# CPU.net
KiCad netlist of a schematic drawn in Altium Designer
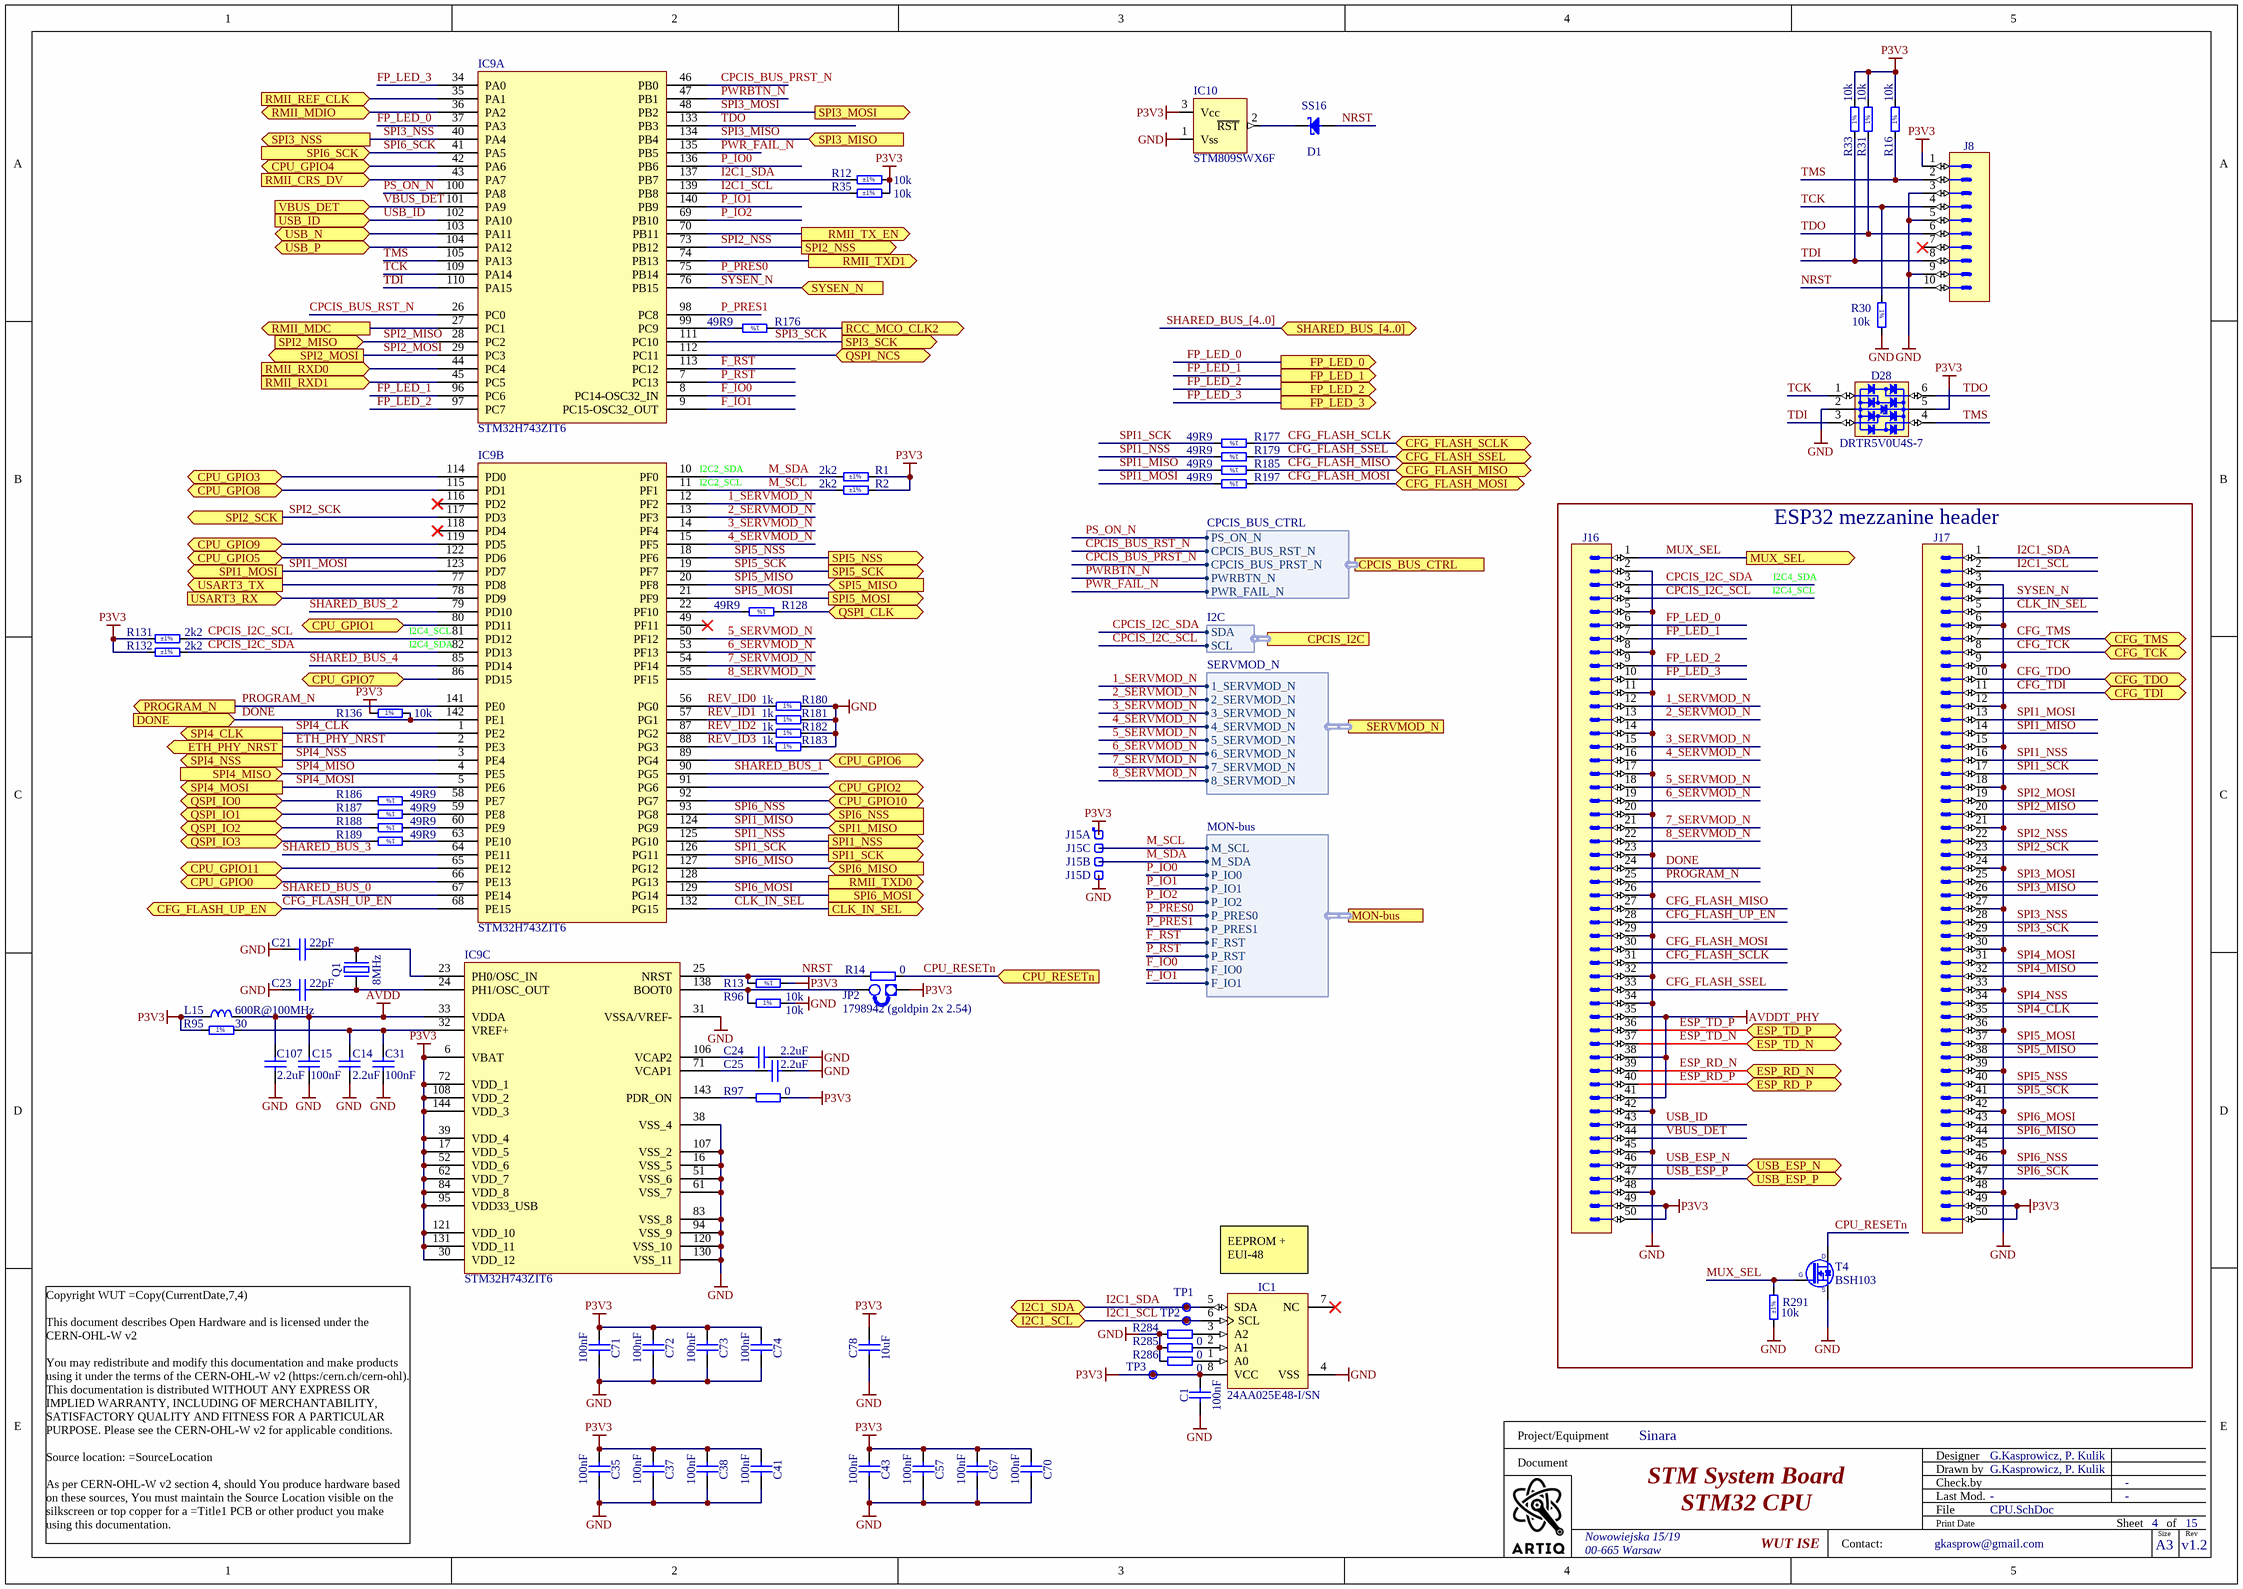
[diagram p0: CPU.SchDoc]

(export (version "E")
  (design (tool "Eeschema 10.0.6"))
  (components
    (comp (ref "C1")
      (value "100nF")
      (footprint "CAPC1005X55N")
      (description "Non-polarised capacitor")
      (fields
        (field (name "PART NUMBER") "CC0402_100NF_16V_10%_X5R")
        (field (name "VOLTAGE") "16V")
        (field (name "AUTHOR") "CERN DEM JLC")
      )
      (libsource (lib "Capacitors") (part "Capacitor - non polarized"))
    )
    (comp (ref "C14")
      (value "2.2uF")
      (footprint "CAPC1608X90N")
      (description "Non-polarised capacitor")
      (fields
        (field (name "PART NUMBER") "CC0603_2.2UF_10V_20%_X7R")
        (field (name "VOLTAGE") "10V")
        (field (name "AUTHOR") "CERN DEM JLC")
      )
      (libsource (lib "Capacitors") (part "Capacitor - non polarized"))
    )
    (comp (ref "C15")
      (value "100nF")
      (footprint "CAPC1005X55N")
      (description "Non-polarised capacitor")
      (fields
        (field (name "PART NUMBER") "CC0402_100NF_16V_10%_X5R")
        (field (name "VOLTAGE") "16V")
        (field (name "AUTHOR") "CERN DEM JLC")
      )
      (libsource (lib "Capacitors") (part "Capacitor - non polarized"))
    )
    (comp (ref "C21")
      (value "22pF")
      (footprint "CAPC1005X55N")
      (description "Non-polarised capacitor")
      (fields
        (field (name "PART NUMBER") "CC0402_22PF_50V_5%_C0G")
        (field (name "VOLTAGE") "50V")
        (field (name "AUTHOR") "CERN DEM JLC")
      )
      (libsource (lib "Capacitors") (part "Capacitor - non polarized"))
    )
    (comp (ref "C23")
      (value "22pF")
      (footprint "CAPC1005X55N")
      (description "Non-polarised capacitor")
      (fields
        (field (name "PART NUMBER") "CC0402_22PF_50V_5%_C0G")
        (field (name "VOLTAGE") "50V")
        (field (name "AUTHOR") "CERN DEM JLC")
      )
      (libsource (lib "Capacitors") (part "Capacitor - non polarized"))
    )
    (comp (ref "C24")
      (value "2.2uF")
      (footprint "CAPC1608X90N")
      (description "Non-polarised capacitor")
      (fields
        (field (name "PART NUMBER") "CC0603_2.2UF_10V_20%_X7R")
        (field (name "VOLTAGE") "10V")
        (field (name "AUTHOR") "CERN DEM JLC")
      )
      (libsource (lib "Capacitors") (part "Capacitor - non polarized"))
    )
    (comp (ref "C25")
      (value "2.2uF")
      (footprint "CAPC1608X90N")
      (description "Non-polarised capacitor")
      (fields
        (field (name "PART NUMBER") "CC0603_2.2UF_10V_20%_X7R")
        (field (name "VOLTAGE") "10V")
        (field (name "AUTHOR") "CERN DEM JLC")
      )
      (libsource (lib "Capacitors") (part "Capacitor - non polarized"))
    )
    (comp (ref "C31")
      (value "100nF")
      (footprint "CAPC1005X55N")
      (description "Non-polarised capacitor")
      (fields
        (field (name "PART NUMBER") "CC0402_100NF_16V_10%_X5R")
        (field (name "VOLTAGE") "16V")
        (field (name "AUTHOR") "CERN DEM JLC")
      )
      (libsource (lib "Capacitors") (part "Capacitor - non polarized"))
    )
    (comp (ref "C35")
      (value "100nF")
      (footprint "CAPC1005X55N")
      (description "Non-polarised capacitor")
      (fields
        (field (name "PART NUMBER") "CC0402_100NF_16V_10%_X5R")
        (field (name "VOLTAGE") "16V")
        (field (name "AUTHOR") "CERN DEM JLC")
      )
      (libsource (lib "Capacitors") (part "Capacitor - non polarized"))
    )
    (comp (ref "C37")
      (value "100nF")
      (footprint "CAPC1005X55N")
      (description "Non-polarised capacitor")
      (fields
        (field (name "PART NUMBER") "CC0402_100NF_16V_10%_X5R")
        (field (name "VOLTAGE") "16V")
        (field (name "AUTHOR") "CERN DEM JLC")
      )
      (libsource (lib "Capacitors") (part "Capacitor - non polarized"))
    )
    (comp (ref "C38")
      (value "100nF")
      (footprint "CAPC1005X55N")
      (description "Non-polarised capacitor")
      (fields
        (field (name "PART NUMBER") "CC0402_100NF_16V_10%_X5R")
        (field (name "VOLTAGE") "16V")
        (field (name "AUTHOR") "CERN DEM JLC")
      )
      (libsource (lib "Capacitors") (part "Capacitor - non polarized"))
    )
    (comp (ref "C41")
      (value "100nF")
      (footprint "CAPC1005X55N")
      (description "Non-polarised capacitor")
      (fields
        (field (name "PART NUMBER") "CC0402_100NF_16V_10%_X5R")
        (field (name "VOLTAGE") "16V")
        (field (name "AUTHOR") "CERN DEM JLC")
      )
      (libsource (lib "Capacitors") (part "Capacitor - non polarized"))
    )
    (comp (ref "C43")
      (value "100nF")
      (footprint "CAPC1005X55N")
      (description "Non-polarised capacitor")
      (fields
        (field (name "PART NUMBER") "CC0402_100NF_16V_10%_X5R")
        (field (name "VOLTAGE") "16V")
        (field (name "AUTHOR") "CERN DEM JLC")
      )
      (libsource (lib "Capacitors") (part "Capacitor - non polarized"))
    )
    (comp (ref "C57")
      (value "100nF")
      (footprint "CAPC1005X55N")
      (description "Non-polarised capacitor")
      (fields
        (field (name "PART NUMBER") "CC0402_100NF_16V_10%_X5R")
        (field (name "VOLTAGE") "16V")
        (field (name "AUTHOR") "CERN DEM JLC")
      )
      (libsource (lib "Capacitors") (part "Capacitor - non polarized"))
    )
    (comp (ref "C67")
      (value "100nF")
      (footprint "CAPC1005X55N")
      (description "Non-polarised capacitor")
      (fields
        (field (name "PART NUMBER") "CC0402_100NF_16V_10%_X5R")
        (field (name "VOLTAGE") "16V")
        (field (name "AUTHOR") "CERN DEM JLC")
      )
      (libsource (lib "Capacitors") (part "Capacitor - non polarized"))
    )
    (comp (ref "C70")
      (value "100nF")
      (footprint "CAPC1005X55N")
      (description "Non-polarised capacitor")
      (fields
        (field (name "PART NUMBER") "CC0402_100NF_16V_10%_X5R")
        (field (name "VOLTAGE") "16V")
        (field (name "AUTHOR") "CERN DEM JLC")
      )
      (libsource (lib "Capacitors") (part "Capacitor - non polarized"))
    )
    (comp (ref "C71")
      (value "100nF")
      (footprint "CAPC1005X55N")
      (description "Non-polarised capacitor")
      (fields
        (field (name "PART NUMBER") "CC0402_100NF_16V_10%_X5R")
        (field (name "VOLTAGE") "16V")
        (field (name "AUTHOR") "CERN DEM JLC")
      )
      (libsource (lib "Capacitors") (part "Capacitor - non polarized"))
    )
    (comp (ref "C72")
      (value "100nF")
      (footprint "CAPC1005X55N")
      (description "Non-polarised capacitor")
      (fields
        (field (name "PART NUMBER") "CC0402_100NF_16V_10%_X5R")
        (field (name "VOLTAGE") "16V")
        (field (name "AUTHOR") "CERN DEM JLC")
      )
      (libsource (lib "Capacitors") (part "Capacitor - non polarized"))
    )
    (comp (ref "C73")
      (value "100nF")
      (footprint "CAPC1005X55N")
      (description "Non-polarised capacitor")
      (fields
        (field (name "PART NUMBER") "CC0402_100NF_16V_10%_X5R")
        (field (name "VOLTAGE") "16V")
        (field (name "AUTHOR") "CERN DEM JLC")
      )
      (libsource (lib "Capacitors") (part "Capacitor - non polarized"))
    )
    (comp (ref "C74")
      (value "100nF")
      (footprint "CAPC1005X55N")
      (description "Non-polarised capacitor")
      (fields
        (field (name "PART NUMBER") "CC0402_100NF_16V_10%_X5R")
        (field (name "VOLTAGE") "16V")
        (field (name "AUTHOR") "CERN DEM JLC")
      )
      (libsource (lib "Capacitors") (part "Capacitor - non polarized"))
    )
    (comp (ref "C78")
      (value "10uF")
      (footprint "CAPC2012X95N")
      (description "Non-polarised capacitor")
      (fields
        (field (name "PART NUMBER") "CC0805_10UF_25V_10%_X5R")
        (field (name "VOLTAGE") "25V")
        (field (name "AUTHOR") "CERN DEM JLC")
      )
      (libsource (lib "Capacitors") (part "Capacitor - non polarized"))
    )
    (comp (ref "C107")
      (value "2.2uF")
      (footprint "CAPC1608X90N")
      (description "Non-polarised capacitor")
      (fields
        (field (name "PART NUMBER") "CC0603_2.2UF_10V_20%_X7R")
        (field (name "VOLTAGE") "10V")
        (field (name "AUTHOR") "CERN DEM JLC")
      )
      (libsource (lib "Capacitors") (part "Capacitor - non polarized"))
    )
    (comp (ref "D1")
      (value "SS16")
      (footprint "DIOM5127X229N")
      (description "Schottky Diode")
      (fields
        (field (name "VOLTAGE") "60V")
        (field (name "POWER") "1A")
        (field (name "AUTHOR") "CERN DEM JLC")
      )
      (libsource (lib "ICs And Semiconductors") (part "Diode Schottky"))
    )
    (comp (ref "D28")
      (value "DRTR5V0U4S-7")
      (footprint "SOT65P210X110-6N")
      (description "Integrated Quad Ultra-Low Capacitance ESD Protection")
      (fields (field (name "MANUFACTURER") "DIODES") (field (name "AUTHOR") "GK"))
      (libsource (lib "Diodes") (part "D_TVS_DRTR5V0U4S-7"))
    )
    (comp (ref "IC1")
      (value "24AA025E48-I/SN")
      (footprint "SOIC127P600X175-8N")
      (description "1.7V-5.5V, 2K I2C™ Serial EEPROMs with EUI-48™ Node Identity")
      (fields (field (name "MANUFACTURER") "MICROCHIP TECHNOLOGY") (field (name "AUTHOR") "CERN DEM MR"))
      (libsource (lib "ICs And Semiconductors") (part "24AA025E48-I/SN"))
    )
    (comp (ref "IC9")
      (value "STM32H743ZIT6")
      (footprint "TSQFP50P2200X2200X160-144N")
      (description "32-bit Arm® Cortex-M7 400MHz MCUs, up to 2MB Flash,\r\n1MB RAM, 46 com. and analog interfaces")
      (fields (field (name "MANUFACTURER") "STMicroelectronics"))
      (libsource (lib "LIBRARY_SCH") (part "UPC_STM32H743ZIT6"))
    )
    (comp (ref "IC10")
      (value "STM809SWX6F")
      (footprint "SOT-23")
      (description "2.93V  Reset circuit")
      (fields (field (name "MANUFACTURER") "STMicroelectronics"))
      (libsource (lib "LIBRARY_SCH") (part "VMON_STM809"))
    )
    (comp (ref "J8")
      (value "Header 10")
      (footprint "SAMTEC_FTSH-105-01-L-DV-K")
      (description "Connector 10 Male")
      (fields
        (field (name "PART NUMBER") "SAMTEC_FTSH-105-01-L-DV-K")
        (field (name "MANUFACTURER") "SAMTEC")
        (field (name "AUTHOR") "CERN DEM BC")
      )
      (libsource (lib "Connectors") (part "Connector 10 Male"))
    )
    (comp (ref "J15")
      (value "Header 4")
      (footprint "SAMTEC_HTSW-104-23-L-S")
      (description "4 Mini Wire-Wrap Contact Strip Header")
      (fields
        (field (name "PART NUMBER") "SAMTEC_HTSW-104-23-L-S")
        (field (name "MANUFACTURER") "SAMTEC")
        (field (name "AUTHOR") "CERN DEM JLC")
      )
      (libsource (lib "Connectors") (part "Wire-Wrap Contact x4"))
    )
    (comp (ref "J16")
      (value "Header 50")
      (footprint "SAMTEC_MTLW-125-07-L-D-250")
      (description "Connector 50 Male")
      (fields
        (field (name "PART NUMBER") "SAMTEC_MTLW-125-07-L-D-250")
        (field (name "MANUFACTURER") "SAMTEC")
        (field (name "AUTHOR") "CERN DEM JLC")
      )
      (libsource (lib "Connectors") (part "Connector 50 Male"))
    )
    (comp (ref "J17")
      (value "Header 50")
      (footprint "SAMTEC_MTLW-125-07-L-D-250")
      (description "Connector 50 Male")
      (fields
        (field (name "PART NUMBER") "SAMTEC_MTLW-125-07-L-D-250")
        (field (name "MANUFACTURER") "SAMTEC")
        (field (name "AUTHOR") "CERN DEM JLC")
      )
      (libsource (lib "Connectors") (part "Connector 50 Male"))
    )
    (comp (ref "JP2")
      (value "1798942 (goldpin 2x 2.54)")
      (footprint "jump")
      (description "Jumper")
      (fields
        (field (name "MANUFACTURER") "Global Connector Technology")
        (field (name "MANUFACTURER PART NUMBER") "BG030-02-A-0650-0300-N-G")
      )
      (libsource (lib "LIBRARY_SCH") (part "JUMPER"))
    )
    (comp (ref "L15")
      (value "600R@100MHz")
      (footprint "INDC1005X55N")
      (description "Inductor")
      (fields
        (field (name "PART NUMBER") "IND0402_MURATA_BLM15HD601SN1")
        (field (name "POWER") "300mA")
        (field (name "AUTHOR") "CERN DEM JLC")
      )
      (libsource (lib "Inductors & Transformers") (part "Inductor"))
    )
    (comp (ref "Q1")
      (value "8MHz")
      (footprint "XTAL_TXC_7A")
      (description "Quartz Crystal")
      (fields
        (field (name "PART NUMBER") "XTAL_8MHZ_TXC_7A-8.000MAAE-T")
        (field (name "MANUFACTURER") "TXC CORPORATION")
        (field (name "AUTHOR") "CERN DEM JLC")
      )
      (libsource (lib "ICs And Semiconductors") (part "Quartz Crystal"))
    )
    (comp (ref "R1")
      (value "2k2")
      (footprint "RESC1005X40N")
      (description "Resistor - 1%")
      (fields
        (field (name "TOLERANCE") "±1%")
        (field (name "PART NUMBER") "R0402_2K2_1%_0.0625W_100PPM")
        (field (name "POWER") "0.0625W")
        (field (name "AUTHOR") "CERN DEM JLC")
      )
      (libsource (lib "Resistors") (part "Resistor - 1%"))
    )
    (comp (ref "R2")
      (value "2k2")
      (footprint "RESC1005X40N")
      (description "Resistor - 1%")
      (fields
        (field (name "TOLERANCE") "±1%")
        (field (name "PART NUMBER") "R0402_2K2_1%_0.0625W_100PPM")
        (field (name "POWER") "0.0625W")
        (field (name "AUTHOR") "CERN DEM JLC")
      )
      (libsource (lib "Resistors") (part "Resistor - 1%"))
    )
    (comp (ref "R12")
      (value "10k")
      (footprint "RESC1005X40N")
      (description "Resistor - 1%")
      (fields
        (field (name "PART NUMBER") "R0402_10K_1%_0.0625W_100PPM")
        (field (name "POWER") "0.0625W")
        (field (name "TOLERANCE") "±1%")
        (field (name "AUTHOR") "CERN DEM JLC")
      )
      (libsource (lib "Resistors") (part "Resistor - 1%"))
    )
    (comp (ref "R13")
      (value "10k")
      (footprint "RESC1005X40N")
      (description "Resistor - 1%")
      (fields
        (field (name "PART NUMBER") "R0402_10K_1%_0.0625W_100PPM")
        (field (name "POWER") "0.0625W")
        (field (name "AUTHOR") "CERN DEM JLC")
      )
      (libsource (lib "Resistors") (part "Resistor - 1%"))
    )
    (comp (ref "R14")
      (value "0")
      (footprint "RESC1005X40N")
      (description "Resistor")
      (fields
        (field (name "PART NUMBER") "R0402_0R_JUMPER")
        (field (name "MANUFACTURER") "GENERIC")
        (field (name "AUTHOR") "CERN DEM JLC")
      )
      (libsource (lib "Resistors") (part "Resistor"))
    )
    (comp (ref "R16")
      (value "10k")
      (footprint "RESC1005X40N")
      (description "Resistor - 1%")
      (fields
        (field (name "PART NUMBER") "R0402_10K_1%_0.0625W_100PPM")
        (field (name "POWER") "0.0625W")
        (field (name "AUTHOR") "CERN DEM JLC")
      )
      (libsource (lib "Resistors") (part "Resistor - 1%"))
    )
    (comp (ref "R30")
      (value "10k")
      (footprint "RESC1005X40N")
      (description "Resistor - 1%")
      (fields
        (field (name "PART NUMBER") "R0402_10K_1%_0.0625W_100PPM")
        (field (name "POWER") "0.0625W")
        (field (name "AUTHOR") "CERN DEM JLC")
      )
      (libsource (lib "Resistors") (part "Resistor - 1%"))
    )
    (comp (ref "R31")
      (value "10k")
      (footprint "RESC1005X40N")
      (description "Resistor - 1%")
      (fields
        (field (name "PART NUMBER") "R0402_10K_1%_0.0625W_100PPM")
        (field (name "POWER") "0.0625W")
        (field (name "AUTHOR") "CERN DEM JLC")
      )
      (libsource (lib "Resistors") (part "Resistor - 1%"))
    )
    (comp (ref "R33")
      (value "10k")
      (footprint "RESC1005X40N")
      (description "Resistor - 1%")
      (fields
        (field (name "PART NUMBER") "R0402_10K_1%_0.0625W_100PPM")
        (field (name "POWER") "0.0625W")
        (field (name "AUTHOR") "CERN DEM JLC")
      )
      (libsource (lib "Resistors") (part "Resistor - 1%"))
    )
    (comp (ref "R35")
      (value "10k")
      (footprint "RESC1005X40N")
      (description "Resistor - 1%")
      (fields
        (field (name "PART NUMBER") "R0402_10K_1%_0.0625W_100PPM")
        (field (name "POWER") "0.0625W")
        (field (name "TOLERANCE") "±1%")
        (field (name "AUTHOR") "CERN DEM JLC")
      )
      (libsource (lib "Resistors") (part "Resistor - 1%"))
    )
    (comp (ref "R95")
      (value "30")
      (footprint "RESC1608X55N")
      (description "Resistor - 1%")
      (fields
        (field (name "PART NUMBER") "R0603_30R_1%_0.1W_100PPM")
        (field (name "POWER") "0.1W")
        (field (name "AUTHOR") "CERN DEM JLC")
      )
      (libsource (lib "Resistors") (part "Resistor - 1%"))
    )
    (comp (ref "R96")
      (value "10k")
      (footprint "RESC1005X40N")
      (description "Resistor - 1%")
      (fields
        (field (name "PART NUMBER") "R0402_10K_1%_0.0625W_100PPM")
        (field (name "POWER") "0.0625W")
        (field (name "AUTHOR") "CERN DEM JLC")
      )
      (libsource (lib "Resistors") (part "Resistor - 1%"))
    )
    (comp (ref "R97")
      (value "0")
      (footprint "RESC1005X40N")
      (description "Resistor")
      (fields
        (field (name "PART NUMBER") "R0402_0R_JUMPER")
        (field (name "MANUFACTURER") "GENERIC")
        (field (name "AUTHOR") "CERN DEM JLC")
      )
      (libsource (lib "Resistors") (part "Resistor"))
    )
    (comp (ref "R128")
      (value "49R9")
      (footprint "RESC1005X40N")
      (description "Resistor - 1%")
      (fields
        (field (name "PART NUMBER") "R0402_49R9_1%_0.0625W_100PPM")
        (field (name "POWER") "0.0625W")
        (field (name "AUTHOR") "CERN DEM JLC")
      )
      (libsource (lib "Resistors") (part "Resistor - 1%"))
    )
    (comp (ref "R131")
      (value "2k2")
      (footprint "RESC1005X40N")
      (description "Resistor - 1%")
      (fields
        (field (name "TOLERANCE") "±1%")
        (field (name "PART NUMBER") "R0402_2K2_1%_0.0625W_100PPM")
        (field (name "POWER") "0.0625W")
        (field (name "AUTHOR") "CERN DEM JLC")
      )
      (libsource (lib "Resistors") (part "Resistor - 1%"))
    )
    (comp (ref "R132")
      (value "2k2")
      (footprint "RESC1005X40N")
      (description "Resistor - 1%")
      (fields
        (field (name "TOLERANCE") "±1%")
        (field (name "PART NUMBER") "R0402_2K2_1%_0.0625W_100PPM")
        (field (name "POWER") "0.0625W")
        (field (name "AUTHOR") "CERN DEM JLC")
      )
      (libsource (lib "Resistors") (part "Resistor - 1%"))
    )
    (comp (ref "R136")
      (value "10k")
      (footprint "RESC1005X40N")
      (description "Resistor - 1%")
      (fields
        (field (name "PART NUMBER") "R0402_10K_1%_0.0625W_100PPM")
        (field (name "POWER") "0.0625W")
        (field (name "AUTHOR") "CERN DEM JLC")
      )
      (libsource (lib "Resistors") (part "Resistor - 1%"))
    )
    (comp (ref "R176")
      (value "49R9")
      (footprint "RESC1005X40N")
      (description "Resistor - 1%")
      (fields
        (field (name "PART NUMBER") "R0402_49R9_1%_0.0625W_100PPM")
        (field (name "POWER") "0.0625W")
        (field (name "AUTHOR") "CERN DEM JLC")
      )
      (libsource (lib "Resistors") (part "Resistor - 1%"))
    )
    (comp (ref "R177")
      (value "49R9")
      (footprint "RESC1005X40N")
      (description "Resistor - 1%")
      (fields
        (field (name "PART NUMBER") "R0402_49R9_1%_0.0625W_100PPM")
        (field (name "POWER") "0.0625W")
        (field (name "AUTHOR") "CERN DEM JLC")
      )
      (libsource (lib "Resistors") (part "Resistor - 1%"))
    )
    (comp (ref "R179")
      (value "49R9")
      (footprint "RESC1005X40N")
      (description "Resistor - 1%")
      (fields
        (field (name "PART NUMBER") "R0402_49R9_1%_0.0625W_100PPM")
        (field (name "POWER") "0.0625W")
        (field (name "AUTHOR") "CERN DEM JLC")
      )
      (libsource (lib "Resistors") (part "Resistor - 1%"))
    )
    (comp (ref "R180")
      (value "1k")
      (footprint "RESC1608X55N")
      (description "Resistor - 1%")
      (fields
        (field (name "PART NUMBER") "R0603_1K_1%_0.1W_100PPM")
        (field (name "POWER") "0.1W")
        (field (name "AUTHOR") "CERN DEM JLC")
      )
      (libsource (lib "Resistors") (part "Resistor - 1%"))
    )
    (comp (ref "R181")
      (value "1k")
      (footprint "RESC1608X55N")
      (description "Resistor - 1%")
      (fields
        (field (name "PART NUMBER") "R0603_1K_1%_0.1W_100PPM")
        (field (name "POWER") "0.1W")
        (field (name "AUTHOR") "CERN DEM JLC")
      )
      (libsource (lib "Resistors") (part "Resistor - 1%"))
    )
    (comp (ref "R182")
      (value "1k")
      (footprint "RESC1608X55N")
      (description "Resistor - 1%")
      (fields
        (field (name "PART NUMBER") "R0603_1K_1%_0.1W_100PPM")
        (field (name "POWER") "0.1W")
        (field (name "AUTHOR") "CERN DEM JLC")
      )
      (libsource (lib "Resistors") (part "Resistor - 1%"))
    )
    (comp (ref "R183")
      (value "1k")
      (footprint "RESC1608X55N")
      (description "Resistor - 1%")
      (fields
        (field (name "PART NUMBER") "R0603_1K_1%_0.1W_100PPM")
        (field (name "POWER") "0.1W")
        (field (name "AUTHOR") "CERN DEM JLC")
      )
      (libsource (lib "Resistors") (part "Resistor - 1%"))
    )
    (comp (ref "R185")
      (value "49R9")
      (footprint "RESC1005X40N")
      (description "Resistor - 1%")
      (fields
        (field (name "PART NUMBER") "R0402_49R9_1%_0.0625W_100PPM")
        (field (name "POWER") "0.0625W")
        (field (name "AUTHOR") "CERN DEM JLC")
      )
      (libsource (lib "Resistors") (part "Resistor - 1%"))
    )
    (comp (ref "R186")
      (value "49R9")
      (footprint "RESC1005X40N")
      (description "Resistor - 1%")
      (fields
        (field (name "PART NUMBER") "R0402_49R9_1%_0.0625W_100PPM")
        (field (name "POWER") "0.0625W")
        (field (name "AUTHOR") "CERN DEM JLC")
      )
      (libsource (lib "Resistors") (part "Resistor - 1%"))
    )
    (comp (ref "R187")
      (value "49R9")
      (footprint "RESC1005X40N")
      (description "Resistor - 1%")
      (fields
        (field (name "PART NUMBER") "R0402_49R9_1%_0.0625W_100PPM")
        (field (name "POWER") "0.0625W")
        (field (name "AUTHOR") "CERN DEM JLC")
      )
      (libsource (lib "Resistors") (part "Resistor - 1%"))
    )
    (comp (ref "R188")
      (value "49R9")
      (footprint "RESC1005X40N")
      (description "Resistor - 1%")
      (fields
        (field (name "PART NUMBER") "R0402_49R9_1%_0.0625W_100PPM")
        (field (name "POWER") "0.0625W")
        (field (name "AUTHOR") "CERN DEM JLC")
      )
      (libsource (lib "Resistors") (part "Resistor - 1%"))
    )
    (comp (ref "R189")
      (value "49R9")
      (footprint "RESC1005X40N")
      (description "Resistor - 1%")
      (fields
        (field (name "PART NUMBER") "R0402_49R9_1%_0.0625W_100PPM")
        (field (name "POWER") "0.0625W")
        (field (name "AUTHOR") "CERN DEM JLC")
      )
      (libsource (lib "Resistors") (part "Resistor - 1%"))
    )
    (comp (ref "R197")
      (value "49R9")
      (footprint "RESC1005X40N")
      (description "Resistor - 1%")
      (fields
        (field (name "PART NUMBER") "R0402_49R9_1%_0.0625W_100PPM")
        (field (name "POWER") "0.0625W")
        (field (name "AUTHOR") "CERN DEM JLC")
      )
      (libsource (lib "Resistors") (part "Resistor - 1%"))
    )
    (comp (ref "R284")
      (value "0")
      (footprint "RESC1005X40N")
      (description "Resistor")
      (fields
        (field (name "PART NUMBER") "R0402_0R_JUMPER")
        (field (name "MANUFACTURER") "GENERIC")
        (field (name "AUTHOR") "CERN DEM JLC")
      )
      (libsource (lib "Resistors") (part "Resistor"))
    )
    (comp (ref "R285")
      (value "0")
      (footprint "RESC1005X40N")
      (description "Resistor")
      (fields
        (field (name "PART NUMBER") "R0402_0R_JUMPER")
        (field (name "MANUFACTURER") "GENERIC")
        (field (name "AUTHOR") "CERN DEM JLC")
      )
      (libsource (lib "Resistors") (part "Resistor"))
    )
    (comp (ref "R286")
      (value "0")
      (footprint "RESC1005X40N")
      (description "Resistor")
      (fields
        (field (name "PART NUMBER") "R0402_0R_JUMPER")
        (field (name "MANUFACTURER") "GENERIC")
        (field (name "AUTHOR") "CERN DEM JLC")
      )
      (libsource (lib "Resistors") (part "Resistor"))
    )
    (comp (ref "R291")
      (value "10k")
      (footprint "RESC1005X40N")
      (description "Resistor - 1%")
      (fields
        (field (name "TOLERANCE") "±1%")
        (field (name "PART NUMBER") "R0402_10K_1%_0.0625W_100PPM")
        (field (name "POWER") "0.0625W")
        (field (name "AUTHOR") "CERN DEM JLC")
      )
      (libsource (lib "Resistors") (part "Resistor - 1%"))
    )
    (comp (ref "T4")
      (value "BSH103")
      (footprint "SOT95P230X110-3N")
      (description "N-CHANNEL MOSFET WITH DIODE")
      (fields (field (name "MANUFACTURER") "NEXPERIA") (field (name "AUTHOR") "CERN DEM JLC"))
      (libsource (lib "ICs And Semiconductors") (part "N-MOSFET-D 1G 2S 3D"))
    )
    (comp (ref "TP1")
      (value "Test Point")
      (footprint "TPS127")
      (fields (field (name "PART NUMBER") "SMD_PAD_1.27X1.27MM") (field (name "AUTHOR") "CERN DEM JLC"))
      (libsource (lib "Eletro-mechanical") (part "Test Point"))
    )
    (comp (ref "TP2")
      (value "Test Point")
      (footprint "TPS127")
      (fields (field (name "PART NUMBER") "SMD_PAD_1.27X1.27MM") (field (name "AUTHOR") "CERN DEM JLC"))
      (libsource (lib "Eletro-mechanical") (part "Test Point"))
    )
    (comp (ref "TP3")
      (value "Test Point")
      (footprint "TPS127")
      (fields (field (name "PART NUMBER") "SMD_PAD_1.27X1.27MM") (field (name "AUTHOR") "CERN DEM JLC"))
      (libsource (lib "Eletro-mechanical") (part "Test Point"))
    )
  )
  (nets
    (net (code "5") (name "/1_SERVMOD_N") (class "Default")
      (node (ref "IC9") (pin "12") (pinfunction "PF2_12") (pintype "passive"))
      (node (ref "J16") (pin "12") (pinfunction "12_12") (pintype "bidirectional"))
    )
    (net (code "6") (name "/2_SERVMOD_N") (class "Default")
      (node (ref "IC9") (pin "13") (pinfunction "PF3_13") (pintype "passive"))
      (node (ref "J16") (pin "13") (pinfunction "13_13") (pintype "bidirectional"))
    )
    (net (code "7") (name "/3_SERVMOD_N") (class "Default")
      (node (ref "IC9") (pin "14") (pinfunction "PF4_14") (pintype "passive"))
      (node (ref "J16") (pin "15") (pinfunction "15_15") (pintype "bidirectional"))
    )
    (net (code "8") (name "/4_SERVMOD_N") (class "Default")
      (node (ref "IC9") (pin "15") (pinfunction "PF5_15") (pintype "passive"))
      (node (ref "J16") (pin "16") (pinfunction "16_16") (pintype "bidirectional"))
    )
    (net (code "9") (name "/5_SERVMOD_N") (class "Default")
      (node (ref "IC9") (pin "50") (pinfunction "PF12_50") (pintype "passive"))
      (node (ref "J16") (pin "18") (pinfunction "18_18") (pintype "bidirectional"))
    )
    (net (code "10") (name "/6_SERVMOD_N") (class "Default")
      (node (ref "IC9") (pin "53") (pinfunction "PF13_53") (pintype "passive"))
      (node (ref "J16") (pin "19") (pinfunction "19_19") (pintype "bidirectional"))
    )
    (net (code "11") (name "/7_SERVMOD_N") (class "Default")
      (node (ref "IC9") (pin "54") (pinfunction "PF14_54") (pintype "passive"))
      (node (ref "J16") (pin "21") (pinfunction "21_21") (pintype "bidirectional"))
    )
    (net (code "12") (name "/8_SERVMOD_N") (class "Default")
      (node (ref "IC9") (pin "55") (pinfunction "PF15_55") (pintype "passive"))
      (node (ref "J16") (pin "22") (pinfunction "22_22") (pintype "bidirectional"))
    )
    (net (code "13") (name "/CFG_FLASH_MISO") (class "Default")
      (node (ref "J16") (pin "27") (pinfunction "27_27") (pintype "bidirectional"))
      (node (ref "R185") (pin "1") (pinfunction "1_1") (pintype "passive"))
    )
    (net (code "14") (name "/CFG_FLASH_MOSI") (class "Default")
      (node (ref "J16") (pin "30") (pinfunction "30_30") (pintype "bidirectional"))
      (node (ref "R197") (pin "1") (pinfunction "1_1") (pintype "passive"))
    )
    (net (code "15") (name "/CFG_FLASH_SCLK") (class "Default")
      (node (ref "J16") (pin "31") (pinfunction "31_31") (pintype "bidirectional"))
      (node (ref "R177") (pin "1") (pinfunction "1_1") (pintype "passive"))
    )
    (net (code "16") (name "/CFG_FLASH_SSEL") (class "Default")
      (node (ref "J16") (pin "33") (pinfunction "33_33") (pintype "bidirectional"))
      (node (ref "R179") (pin "1") (pinfunction "1_1") (pintype "passive"))
    )
    (net (code "17") (name "/CFG_FLASH_UP_EN") (class "Default")
      (node (ref "IC9") (pin "68") (pinfunction "PE15_68") (pintype "passive"))
      (node (ref "J16") (pin "28") (pinfunction "28_28") (pintype "bidirectional"))
    )
    (net (code "18") (name "/CFG_TCK") (class "Default")
      (node (ref "J17") (pin "8") (pinfunction "8_8") (pintype "bidirectional"))
    )
    (net (code "19") (name "/CFG_TDI") (class "Default")
      (node (ref "J17") (pin "11") (pinfunction "11_11") (pintype "bidirectional"))
    )
    (net (code "20") (name "/CFG_TDO") (class "Default")
      (node (ref "J17") (pin "10") (pinfunction "10_10") (pintype "bidirectional"))
    )
    (net (code "21") (name "/CFG_TMS") (class "Default")
      (node (ref "J17") (pin "7") (pinfunction "7_7") (pintype "bidirectional"))
    )
    (net (code "22") (name "/CLK_IN_SEL") (class "Default")
      (node (ref "IC9") (pin "132") (pinfunction "PG15_132") (pintype "passive"))
      (node (ref "J17") (pin "5") (pinfunction "5_5") (pintype "bidirectional"))
    )
    (net (code "23") (name "/CPCIS_BUS_PRST_N") (class "Default")
      (node (ref "IC9") (pin "46") (pinfunction "PB0_46") (pintype "passive"))
    )
    (net (code "24") (name "/CPCIS_BUS_RST_N") (class "Default")
      (node (ref "IC9") (pin "26") (pinfunction "PC0_26") (pintype "passive"))
    )
    (net (code "25") (name "/CPCIS_I2C_SCL") (class "Default")
      (node (ref "IC9") (pin "81") (pinfunction "PD12_81") (pintype "passive"))
      (node (ref "J16") (pin "4") (pinfunction "4_4") (pintype "bidirectional"))
      (node (ref "R131") (pin "2") (pinfunction "2_2") (pintype "passive"))
    )
    (net (code "26") (name "/CPCIS_I2C_SDA") (class "Default")
      (node (ref "IC9") (pin "82") (pinfunction "PD13_82") (pintype "passive"))
      (node (ref "J16") (pin "3") (pinfunction "3_3") (pintype "bidirectional"))
      (node (ref "R132") (pin "2") (pinfunction "2_2") (pintype "passive"))
    )
    (net (code "27") (name "/CPU_GPIO0") (class "Default")
      (node (ref "IC9") (pin "66") (pinfunction "PE13_66") (pintype "passive"))
    )
    (net (code "28") (name "/CPU_GPIO1") (class "Default")
      (node (ref "IC9") (pin "80") (pinfunction "PD11_80") (pintype "passive"))
    )
    (net (code "29") (name "/CPU_GPIO2") (class "Default")
      (node (ref "IC9") (pin "91") (pinfunction "PG6_91") (pintype "passive"))
    )
    (net (code "30") (name "/CPU_GPIO3") (class "Default")
      (node (ref "IC9") (pin "114") (pinfunction "PD0_114") (pintype "passive"))
    )
    (net (code "31") (name "/CPU_GPIO4") (class "Default")
      (node (ref "IC9") (pin "42") (pinfunction "PA6_42") (pintype "passive"))
    )
    (net (code "32") (name "/CPU_GPIO5") (class "Default")
      (node (ref "IC9") (pin "122") (pinfunction "PD6_122") (pintype "passive"))
    )
    (net (code "33") (name "/CPU_GPIO6") (class "Default")
      (node (ref "IC9") (pin "89") (pinfunction "PG4_89") (pintype "passive"))
    )
    (net (code "34") (name "/CPU_GPIO7") (class "Default")
      (node (ref "IC9") (pin "86") (pinfunction "PD15_86") (pintype "passive"))
    )
    (net (code "35") (name "/CPU_GPIO8") (class "Default")
      (node (ref "IC9") (pin "115") (pinfunction "PD1_115") (pintype "passive"))
    )
    (net (code "36") (name "/CPU_GPIO9") (class "Default")
      (node (ref "IC9") (pin "119") (pinfunction "PD5_119") (pintype "passive"))
    )
    (net (code "37") (name "/CPU_GPIO10") (class "Default")
      (node (ref "IC9") (pin "92") (pinfunction "PG7_92") (pintype "passive"))
    )
    (net (code "38") (name "/CPU_GPIO11") (class "Default")
      (node (ref "IC9") (pin "65") (pinfunction "PE12_65") (pintype "passive"))
    )
    (net (code "39") (name "/CPU_RESETn") (class "Default")
      (node (ref "R14") (pin "2") (pinfunction "2_2") (pintype "passive"))
      (node (ref "T4") (pin "3") (pinfunction "D_3") (pintype "passive"))
    )
    (net (code "40") (name "/DONE") (class "Default")
      (node (ref "IC9") (pin "142") (pinfunction "PE1_142") (pintype "passive"))
      (node (ref "J16") (pin "24") (pinfunction "24_24") (pintype "bidirectional"))
      (node (ref "R136") (pin "2") (pinfunction "2_2") (pintype "passive"))
    )
    (net (code "41") (name "/ESP_RD_N") (class "Default")
      (node (ref "J16") (pin "39") (pinfunction "39_39") (pintype "bidirectional"))
    )
    (net (code "42") (name "/ESP_RD_P") (class "Default")
      (node (ref "J16") (pin "40") (pinfunction "40_40") (pintype "bidirectional"))
    )
    (net (code "43") (name "/ESP_TD_N") (class "Default")
      (node (ref "J16") (pin "37") (pinfunction "37_37") (pintype "bidirectional"))
    )
    (net (code "44") (name "/ESP_TD_P") (class "Default")
      (node (ref "J16") (pin "36") (pinfunction "36_36") (pintype "bidirectional"))
    )
    (net (code "45") (name "/ETH_PHY_NRST") (class "Default")
      (node (ref "IC9") (pin "2") (pinfunction "PE3_2") (pintype "passive"))
    )
    (net (code "46") (name "/FP_LED_0") (class "Default")
      (node (ref "IC9") (pin "37") (pinfunction "PA3_37") (pintype "passive"))
      (node (ref "J16") (pin "6") (pinfunction "6_6") (pintype "bidirectional"))
    )
    (net (code "47") (name "/FP_LED_1") (class "Default")
      (node (ref "IC9") (pin "96") (pinfunction "PC6_96") (pintype "passive"))
      (node (ref "J16") (pin "7") (pinfunction "7_7") (pintype "bidirectional"))
    )
    (net (code "48") (name "/FP_LED_2") (class "Default")
      (node (ref "IC9") (pin "97") (pinfunction "PC7_97") (pintype "passive"))
      (node (ref "J16") (pin "9") (pinfunction "9_9") (pintype "bidirectional"))
    )
    (net (code "49") (name "/FP_LED_3") (class "Default")
      (node (ref "IC9") (pin "34") (pinfunction "PA0_34") (pintype "passive"))
      (node (ref "J16") (pin "10") (pinfunction "10_10") (pintype "bidirectional"))
    )
    (net (code "50") (name "/F_IO0") (class "Default")
      (node (ref "IC9") (pin "8") (pinfunction "PC14-OSC32_IN_8") (pintype "passive"))
    )
    (net (code "51") (name "/F_IO1") (class "Default")
      (node (ref "IC9") (pin "9") (pinfunction "PC15-OSC32_OUT_9") (pintype "passive"))
    )
    (net (code "52") (name "/F_RST") (class "Default")
      (node (ref "IC9") (pin "113") (pinfunction "PC12_113") (pintype "passive"))
    )
    (net (code "53") (name "/I2C1_SCL") (class "Default")
      (node (ref "IC1") (pin "6") (pinfunction "SCL_6") (pintype "input"))
      (node (ref "IC9") (pin "139") (pinfunction "PB8_139") (pintype "passive"))
      (node (ref "J17") (pin "2") (pinfunction "2_2") (pintype "bidirectional"))
      (node (ref "R35") (pin "1") (pinfunction "1_1") (pintype "passive"))
      (node (ref "TP2") (pin "1") (pinfunction "1_1") (pintype "bidirectional"))
    )
    (net (code "54") (name "/I2C1_SDA") (class "Default")
      (node (ref "IC1") (pin "5") (pinfunction "SDA_5") (pintype "bidirectional"))
      (node (ref "IC9") (pin "137") (pinfunction "PB7_137") (pintype "passive"))
      (node (ref "J17") (pin "1") (pinfunction "1_1") (pintype "bidirectional"))
      (node (ref "R12") (pin "1") (pinfunction "1_1") (pintype "passive"))
      (node (ref "TP1") (pin "1") (pinfunction "1_1") (pintype "bidirectional"))
    )
    (net (code "55") (name "/MUX_SEL") (class "Default")
      (node (ref "J16") (pin "1") (pinfunction "1_1") (pintype "bidirectional"))
      (node (ref "R291") (pin "2") (pinfunction "2_2") (pintype "passive"))
      (node (ref "T4") (pin "1") (pinfunction "G_1") (pintype "passive"))
    )
    (net (code "56") (name "/M_SCL") (class "Default")
      (node (ref "IC9") (pin "11") (pinfunction "PF1_11") (pintype "passive"))
      (node (ref "J15") (pin "3") (pinfunction "3_3") (pintype "bidirectional"))
      (node (ref "R2") (pin "2") (pinfunction "2_2") (pintype "passive"))
    )
    (net (code "57") (name "/M_SDA") (class "Default")
      (node (ref "IC9") (pin "10") (pinfunction "PF0_10") (pintype "passive"))
      (node (ref "J15") (pin "2") (pinfunction "2_2") (pintype "bidirectional"))
      (node (ref "R1") (pin "2") (pinfunction "2_2") (pintype "passive"))
    )
    (net (code "58") (name "/NRST") (class "Default")
      (node (ref "D1") (pin "2") (pinfunction "A_2") (pintype "passive"))
      (node (ref "IC9") (pin "25") (pinfunction "NRST_25") (pintype "passive"))
      (node (ref "J8") (pin "10") (pinfunction "10_10") (pintype "bidirectional"))
      (node (ref "R13") (pin "2") (pinfunction "2_2") (pintype "passive"))
      (node (ref "R14") (pin "1") (pinfunction "1_1") (pintype "passive"))
    )
    (net (code "59") (name "/PROGRAM_N") (class "Default")
      (node (ref "IC9") (pin "141") (pinfunction "PE0_141") (pintype "passive"))
      (node (ref "J16") (pin "25") (pinfunction "25_25") (pintype "bidirectional"))
    )
    (net (code "60") (name "/PS_ON_N") (class "Default")
      (node (ref "IC9") (pin "100") (pinfunction "PA8_100") (pintype "passive"))
    )
    (net (code "61") (name "/PWRBTN_N") (class "Default")
      (node (ref "IC9") (pin "47") (pinfunction "PB1_47") (pintype "passive"))
    )
    (net (code "62") (name "/PWR_FAIL_N") (class "Default")
      (node (ref "IC9") (pin "135") (pinfunction "PB5_135") (pintype "passive"))
    )
    (net (code "63") (name "/P_IO0") (class "Default")
      (node (ref "IC9") (pin "136") (pinfunction "PB6_136") (pintype "passive"))
    )
    (net (code "64") (name "/P_IO1") (class "Default")
      (node (ref "IC9") (pin "140") (pinfunction "PB9_140") (pintype "passive"))
    )
    (net (code "65") (name "/P_IO2") (class "Default")
      (node (ref "IC9") (pin "69") (pinfunction "PB10_69") (pintype "passive"))
    )
    (net (code "66") (name "/P_PRES0") (class "Default")
      (node (ref "IC9") (pin "75") (pinfunction "PB14_75") (pintype "passive"))
    )
    (net (code "67") (name "/P_PRES1") (class "Default")
      (node (ref "IC9") (pin "98") (pinfunction "PC8_98") (pintype "passive"))
    )
    (net (code "68") (name "/P_RST") (class "Default")
      (node (ref "IC9") (pin "7") (pinfunction "PC13_7") (pintype "passive"))
    )
    (net (code "69") (name "/QSPI_CLK") (class "Default")
      (node (ref "R128") (pin "1") (pinfunction "1_1") (pintype "passive"))
    )
    (net (code "70") (name "/QSPI_IO0") (class "Default")
      (node (ref "R186") (pin "2") (pinfunction "2_2") (pintype "passive"))
    )
    (net (code "71") (name "/QSPI_IO1") (class "Default")
      (node (ref "R187") (pin "2") (pinfunction "2_2") (pintype "passive"))
    )
    (net (code "72") (name "/QSPI_IO2") (class "Default")
      (node (ref "R188") (pin "2") (pinfunction "2_2") (pintype "passive"))
    )
    (net (code "73") (name "/QSPI_IO3") (class "Default")
      (node (ref "R189") (pin "2") (pinfunction "2_2") (pintype "passive"))
    )
    (net (code "74") (name "/QSPI_NCS") (class "Default")
      (node (ref "IC9") (pin "112") (pinfunction "PC11_112") (pintype "passive"))
    )
    (net (code "75") (name "/RCC_MCO_CLK2") (class "Default")
      (node (ref "R176") (pin "1") (pinfunction "1_1") (pintype "passive"))
    )
    (net (code "76") (name "/REV_ID0") (class "Default")
      (node (ref "IC9") (pin "56") (pinfunction "PG0_56") (pintype "passive"))
      (node (ref "R180") (pin "1") (pinfunction "1_1") (pintype "passive"))
    )
    (net (code "77") (name "/REV_ID1") (class "Default")
      (node (ref "IC9") (pin "57") (pinfunction "PG1_57") (pintype "passive"))
      (node (ref "R181") (pin "1") (pinfunction "1_1") (pintype "passive"))
    )
    (net (code "78") (name "/REV_ID2") (class "Default")
      (node (ref "IC9") (pin "87") (pinfunction "PG2_87") (pintype "passive"))
      (node (ref "R182") (pin "1") (pinfunction "1_1") (pintype "passive"))
    )
    (net (code "79") (name "/REV_ID3") (class "Default")
      (node (ref "IC9") (pin "88") (pinfunction "PG3_88") (pintype "passive"))
      (node (ref "R183") (pin "1") (pinfunction "1_1") (pintype "passive"))
    )
    (net (code "80") (name "/RMII_CRS_DV") (class "Default")
      (node (ref "IC9") (pin "43") (pinfunction "PA7_43") (pintype "passive"))
    )
    (net (code "81") (name "/RMII_MDC") (class "Default")
      (node (ref "IC9") (pin "27") (pinfunction "PC1_27") (pintype "passive"))
    )
    (net (code "82") (name "/RMII_MDIO") (class "Default")
      (node (ref "IC9") (pin "36") (pinfunction "PA2_36") (pintype "passive"))
    )
    (net (code "83") (name "/RMII_REF_CLK") (class "Default")
      (node (ref "IC9") (pin "35") (pinfunction "PA1_35") (pintype "passive"))
    )
    (net (code "84") (name "/RMII_RXD0") (class "Default")
      (node (ref "IC9") (pin "44") (pinfunction "PC4_44") (pintype "passive"))
    )
    (net (code "85") (name "/RMII_RXD1") (class "Default")
      (node (ref "IC9") (pin "45") (pinfunction "PC5_45") (pintype "passive"))
    )
    (net (code "86") (name "/RMII_TXD0") (class "Default")
      (node (ref "IC9") (pin "128") (pinfunction "PG13_128") (pintype "passive"))
    )
    (net (code "87") (name "/RMII_TXD1") (class "Default")
      (node (ref "IC9") (pin "74") (pinfunction "PB13_74") (pintype "passive"))
    )
    (net (code "88") (name "/RMII_TX_EN") (class "Default")
      (node (ref "IC9") (pin "70") (pinfunction "PB11_70") (pintype "passive"))
    )
    (net (code "89") (name "/SHARED_BUS_0") (class "Default")
      (node (ref "IC9") (pin "67") (pinfunction "PE14_67") (pintype "passive"))
    )
    (net (code "90") (name "/SHARED_BUS_1") (class "Default")
      (node (ref "IC9") (pin "90") (pinfunction "PG5_90") (pintype "passive"))
    )
    (net (code "91") (name "/SHARED_BUS_2") (class "Default")
      (node (ref "IC9") (pin "79") (pinfunction "PD10_79") (pintype "passive"))
    )
    (net (code "92") (name "/SHARED_BUS_3") (class "Default")
      (node (ref "IC9") (pin "64") (pinfunction "PE11_64") (pintype "passive"))
    )
    (net (code "93") (name "/SHARED_BUS_4") (class "Default")
      (node (ref "IC9") (pin "85") (pinfunction "PD14_85") (pintype "passive"))
    )
    (net (code "95") (name "/SPI1_MISO") (class "Default")
      (node (ref "IC9") (pin "124") (pinfunction "PG9_124") (pintype "passive"))
      (node (ref "J17") (pin "14") (pinfunction "14_14") (pintype "bidirectional"))
      (node (ref "R185") (pin "2") (pinfunction "2_2") (pintype "passive"))
    )
    (net (code "96") (name "/SPI1_MOSI") (class "Default")
      (node (ref "IC9") (pin "123") (pinfunction "PD7_123") (pintype "passive"))
      (node (ref "J17") (pin "13") (pinfunction "13_13") (pintype "bidirectional"))
      (node (ref "R197") (pin "2") (pinfunction "2_2") (pintype "passive"))
    )
    (net (code "97") (name "/SPI1_NSS") (class "Default")
      (node (ref "IC9") (pin "125") (pinfunction "PG10_125") (pintype "passive"))
      (node (ref "J17") (pin "16") (pinfunction "16_16") (pintype "bidirectional"))
      (node (ref "R179") (pin "2") (pinfunction "2_2") (pintype "passive"))
    )
    (net (code "98") (name "/SPI1_SCK") (class "Default")
      (node (ref "IC9") (pin "126") (pinfunction "PG11_126") (pintype "passive"))
      (node (ref "J17") (pin "17") (pinfunction "17_17") (pintype "bidirectional"))
      (node (ref "R177") (pin "2") (pinfunction "2_2") (pintype "passive"))
    )
    (net (code "99") (name "/SPI2_MISO") (class "Default")
      (node (ref "IC9") (pin "28") (pinfunction "PC2_28") (pintype "passive"))
      (node (ref "J17") (pin "20") (pinfunction "20_20") (pintype "bidirectional"))
    )
    (net (code "100") (name "/SPI2_MOSI") (class "Default")
      (node (ref "IC9") (pin "29") (pinfunction "PC3_29") (pintype "passive"))
      (node (ref "J17") (pin "19") (pinfunction "19_19") (pintype "bidirectional"))
    )
    (net (code "101") (name "/SPI2_NSS") (class "Default")
      (node (ref "IC9") (pin "73") (pinfunction "PB12_73") (pintype "passive"))
      (node (ref "J17") (pin "22") (pinfunction "22_22") (pintype "bidirectional"))
    )
    (net (code "102") (name "/SPI2_SCK") (class "Default")
      (node (ref "IC9") (pin "117") (pinfunction "PD3_117") (pintype "passive"))
      (node (ref "J17") (pin "23") (pinfunction "23_23") (pintype "bidirectional"))
    )
    (net (code "103") (name "/SPI3_MISO") (class "Default")
      (node (ref "IC9") (pin "134") (pinfunction "PB4_134") (pintype "passive"))
      (node (ref "J17") (pin "26") (pinfunction "26_26") (pintype "bidirectional"))
    )
    (net (code "104") (name "/SPI3_MOSI") (class "Default")
      (node (ref "IC9") (pin "48") (pinfunction "PB2_48") (pintype "passive"))
      (node (ref "J17") (pin "25") (pinfunction "25_25") (pintype "bidirectional"))
    )
    (net (code "105") (name "/SPI3_NSS") (class "Default")
      (node (ref "IC9") (pin "40") (pinfunction "PA4_40") (pintype "passive"))
      (node (ref "J17") (pin "28") (pinfunction "28_28") (pintype "bidirectional"))
    )
    (net (code "106") (name "/SPI3_SCK") (class "Default")
      (node (ref "IC9") (pin "111") (pinfunction "PC10_111") (pintype "passive"))
      (node (ref "J17") (pin "29") (pinfunction "29_29") (pintype "bidirectional"))
    )
    (net (code "107") (name "/SPI4_CLK") (class "Default")
      (node (ref "IC9") (pin "1") (pinfunction "PE2_1") (pintype "passive"))
      (node (ref "J17") (pin "35") (pinfunction "35_35") (pintype "bidirectional"))
    )
    (net (code "108") (name "/SPI4_MISO") (class "Default")
      (node (ref "IC9") (pin "4") (pinfunction "PE5_4") (pintype "passive"))
      (node (ref "J17") (pin "32") (pinfunction "32_32") (pintype "bidirectional"))
    )
    (net (code "109") (name "/SPI4_MOSI") (class "Default")
      (node (ref "IC9") (pin "5") (pinfunction "PE6_5") (pintype "passive"))
      (node (ref "J17") (pin "31") (pinfunction "31_31") (pintype "bidirectional"))
    )
    (net (code "110") (name "/SPI4_NSS") (class "Default")
      (node (ref "IC9") (pin "3") (pinfunction "PE4_3") (pintype "passive"))
      (node (ref "J17") (pin "34") (pinfunction "34_34") (pintype "bidirectional"))
    )
    (net (code "111") (name "/SPI5_MISO") (class "Default")
      (node (ref "IC9") (pin "20") (pinfunction "PF8_20") (pintype "passive"))
      (node (ref "J17") (pin "38") (pinfunction "38_38") (pintype "bidirectional"))
    )
    (net (code "112") (name "/SPI5_MOSI") (class "Default")
      (node (ref "IC9") (pin "21") (pinfunction "PF9_21") (pintype "passive"))
      (node (ref "J17") (pin "37") (pinfunction "37_37") (pintype "bidirectional"))
    )
    (net (code "113") (name "/SPI5_NSS") (class "Default")
      (node (ref "IC9") (pin "18") (pinfunction "PF6_18") (pintype "passive"))
      (node (ref "J17") (pin "40") (pinfunction "40_40") (pintype "bidirectional"))
    )
    (net (code "114") (name "/SPI5_SCK") (class "Default")
      (node (ref "IC9") (pin "19") (pinfunction "PF7_19") (pintype "passive"))
      (node (ref "J17") (pin "41") (pinfunction "41_41") (pintype "bidirectional"))
    )
    (net (code "115") (name "/SPI6_MISO") (class "Default")
      (node (ref "IC9") (pin "127") (pinfunction "PG12_127") (pintype "passive"))
      (node (ref "J17") (pin "44") (pinfunction "44_44") (pintype "bidirectional"))
    )
    (net (code "116") (name "/SPI6_MOSI") (class "Default")
      (node (ref "IC9") (pin "129") (pinfunction "PG14_129") (pintype "passive"))
      (node (ref "J17") (pin "43") (pinfunction "43_43") (pintype "bidirectional"))
    )
    (net (code "117") (name "/SPI6_NSS") (class "Default")
      (node (ref "IC9") (pin "93") (pinfunction "PG8_93") (pintype "passive"))
      (node (ref "J17") (pin "46") (pinfunction "46_46") (pintype "bidirectional"))
    )
    (net (code "118") (name "/SPI6_SCK") (class "Default")
      (node (ref "IC9") (pin "41") (pinfunction "PA5_41") (pintype "passive"))
      (node (ref "J17") (pin "47") (pinfunction "47_47") (pintype "bidirectional"))
    )
    (net (code "119") (name "/SYSEN_N") (class "Default")
      (node (ref "IC9") (pin "76") (pinfunction "PB15_76") (pintype "passive"))
      (node (ref "J17") (pin "4") (pinfunction "4_4") (pintype "bidirectional"))
    )
    (net (code "120") (name "/TCK") (class "Default")
      (node (ref "D28") (pin "1") (pinfunction "I/O1_1") (pintype "bidirectional"))
      (node (ref "IC9") (pin "109") (pinfunction "PA14_109") (pintype "passive"))
      (node (ref "J8") (pin "4") (pinfunction "4_4") (pintype "bidirectional"))
      (node (ref "R30") (pin "2") (pinfunction "2_2") (pintype "passive"))
    )
    (net (code "121") (name "/TDI") (class "Default")
      (node (ref "D28") (pin "3") (pinfunction "I/O2_3") (pintype "bidirectional"))
      (node (ref "IC9") (pin "110") (pinfunction "PA15_110") (pintype "passive"))
      (node (ref "J8") (pin "8") (pinfunction "8_8") (pintype "bidirectional"))
      (node (ref "R33") (pin "2") (pinfunction "2_2") (pintype "passive"))
    )
    (net (code "122") (name "/TDO") (class "Default")
      (node (ref "D28") (pin "6") (pinfunction "I/O4_6") (pintype "bidirectional"))
      (node (ref "IC9") (pin "133") (pinfunction "PB3_133") (pintype "passive"))
      (node (ref "J8") (pin "6") (pinfunction "6_6") (pintype "bidirectional"))
      (node (ref "R31") (pin "2") (pinfunction "2_2") (pintype "passive"))
    )
    (net (code "123") (name "/TMS") (class "Default")
      (node (ref "D28") (pin "4") (pinfunction "I/O3_4") (pintype "bidirectional"))
      (node (ref "IC9") (pin "105") (pinfunction "PA13_105") (pintype "passive"))
      (node (ref "J8") (pin "2") (pinfunction "2_2") (pintype "bidirectional"))
      (node (ref "R16") (pin "2") (pinfunction "2_2") (pintype "passive"))
    )
    (net (code "124") (name "/USART3_RX") (class "Default")
      (node (ref "IC9") (pin "78") (pinfunction "PD9_78") (pintype "passive"))
    )
    (net (code "125") (name "/USART3_TX") (class "Default")
      (node (ref "IC9") (pin "77") (pinfunction "PD8_77") (pintype "passive"))
    )
    (net (code "126") (name "/USB_ESP_N") (class "Default")
      (node (ref "J16") (pin "46") (pinfunction "46_46") (pintype "bidirectional"))
    )
    (net (code "127") (name "/USB_ESP_P") (class "Default")
      (node (ref "J16") (pin "47") (pinfunction "47_47") (pintype "bidirectional"))
    )
    (net (code "128") (name "/USB_ID") (class "Default")
      (node (ref "IC9") (pin "102") (pinfunction "PA10_102") (pintype "passive"))
      (node (ref "J16") (pin "43") (pinfunction "43_43") (pintype "bidirectional"))
    )
    (net (code "129") (name "/USB_N") (class "Default")
      (node (ref "IC9") (pin "103") (pinfunction "PA11_103") (pintype "passive"))
    )
    (net (code "130") (name "/USB_P") (class "Default")
      (node (ref "IC9") (pin "104") (pinfunction "PA12_104") (pintype "passive"))
    )
    (net (code "131") (name "/VBUS_DET") (class "Default")
      (node (ref "IC9") (pin "101") (pinfunction "PA9_101") (pintype "passive"))
      (node (ref "J16") (pin "44") (pinfunction "44_44") (pintype "bidirectional"))
    )
    (net (code "136") (name "AVDD") (class "Default")
      (node (ref "C107") (pin "2") (pinfunction "2_2") (pintype "passive"))
      (node (ref "C15") (pin "1") (pinfunction "1_1") (pintype "passive"))
      (node (ref "IC9") (pin "33") (pinfunction "VDDA_33") (pintype "passive"))
      (node (ref "L15") (pin "2") (pinfunction "2_2") (pintype "passive"))
    )
    (net (code "137") (name "AVDDT_PHY") (class "Default")
      (node (ref "J16") (pin "35") (pinfunction "35_35") (pintype "bidirectional"))
      (node (ref "J16") (pin "38") (pinfunction "38_38") (pintype "bidirectional"))
      (node (ref "J16") (pin "41") (pinfunction "41_41") (pintype "bidirectional"))
    )
    (net (code "138") (name "GND") (class "Default")
      (node (ref "C1") (pin "1") (pinfunction "1_1") (pintype "passive"))
      (node (ref "C107") (pin "1") (pinfunction "1_1") (pintype "passive"))
      (node (ref "C14") (pin "1") (pinfunction "1_1") (pintype "passive"))
      (node (ref "C15") (pin "2") (pinfunction "2_2") (pintype "passive"))
      (node (ref "C21") (pin "1") (pinfunction "1_1") (pintype "passive"))
      (node (ref "C23") (pin "1") (pinfunction "1_1") (pintype "passive"))
      (node (ref "C24") (pin "2") (pinfunction "2_2") (pintype "passive"))
      (node (ref "C25") (pin "2") (pinfunction "2_2") (pintype "passive"))
      (node (ref "C31") (pin "2") (pinfunction "2_2") (pintype "passive"))
      (node (ref "C35") (pin "2") (pinfunction "2_2") (pintype "passive"))
      (node (ref "C37") (pin "2") (pinfunction "2_2") (pintype "passive"))
      (node (ref "C38") (pin "2") (pinfunction "2_2") (pintype "passive"))
      (node (ref "C41") (pin "2") (pinfunction "2_2") (pintype "passive"))
      (node (ref "C43") (pin "2") (pinfunction "2_2") (pintype "passive"))
      (node (ref "C57") (pin "2") (pinfunction "2_2") (pintype "passive"))
      (node (ref "C67") (pin "2") (pinfunction "2_2") (pintype "passive"))
      (node (ref "C70") (pin "2") (pinfunction "2_2") (pintype "passive"))
      (node (ref "C71") (pin "2") (pinfunction "2_2") (pintype "passive"))
      (node (ref "C72") (pin "2") (pinfunction "2_2") (pintype "passive"))
      (node (ref "C73") (pin "2") (pinfunction "2_2") (pintype "passive"))
      (node (ref "C74") (pin "2") (pinfunction "2_2") (pintype "passive"))
      (node (ref "C78") (pin "1") (pinfunction "1_1") (pintype "passive"))
      (node (ref "D28") (pin "2") (pinfunction "GND_2") (pintype "power_in"))
      (node (ref "IC1") (pin "4") (pinfunction "VSS_4") (pintype "power_in"))
      (node (ref "IC10") (pin "1") (pinfunction "Vss_1") (pintype "power_in"))
      (node (ref "IC9") (pin "107") (pinfunction "VSS_2_107") (pintype "passive"))
      (node (ref "IC9") (pin "120") (pinfunction "VSS_10_120") (pintype "passive"))
      (node (ref "IC9") (pin "130") (pinfunction "VSS_11_130") (pintype "passive"))
      (node (ref "IC9") (pin "16") (pinfunction "VSS_5_16") (pintype "passive"))
      (node (ref "IC9") (pin "31") (pinfunction "VSSA/VREF-_31") (pintype "passive"))
      (node (ref "IC9") (pin "38") (pinfunction "VSS_4_38") (pintype "passive"))
      (node (ref "IC9") (pin "51") (pinfunction "VSS_6_51") (pintype "passive"))
      (node (ref "IC9") (pin "61") (pinfunction "VSS_7_61") (pintype "passive"))
      (node (ref "IC9") (pin "83") (pinfunction "VSS_8_83") (pintype "passive"))
      (node (ref "IC9") (pin "94") (pinfunction "VSS_9_94") (pintype "passive"))
      (node (ref "J15") (pin "4") (pinfunction "4_4") (pintype "bidirectional"))
      (node (ref "J16") (pin "11") (pinfunction "11_11") (pintype "bidirectional"))
      (node (ref "J16") (pin "14") (pinfunction "14_14") (pintype "bidirectional"))
      (node (ref "J16") (pin "17") (pinfunction "17_17") (pintype "bidirectional"))
      (node (ref "J16") (pin "2") (pinfunction "2_2") (pintype "bidirectional"))
      (node (ref "J16") (pin "20") (pinfunction "20_20") (pintype "bidirectional"))
      (node (ref "J16") (pin "23") (pinfunction "23_23") (pintype "bidirectional"))
      (node (ref "J16") (pin "26") (pinfunction "26_26") (pintype "bidirectional"))
      (node (ref "J16") (pin "29") (pinfunction "29_29") (pintype "bidirectional"))
      (node (ref "J16") (pin "32") (pinfunction "32_32") (pintype "bidirectional"))
      (node (ref "J16") (pin "34") (pinfunction "34_34") (pintype "bidirectional"))
      (node (ref "J16") (pin "42") (pinfunction "42_42") (pintype "bidirectional"))
      (node (ref "J16") (pin "45") (pinfunction "45_45") (pintype "bidirectional"))
      (node (ref "J16") (pin "48") (pinfunction "48_48") (pintype "bidirectional"))
      (node (ref "J16") (pin "5") (pinfunction "5_5") (pintype "bidirectional"))
      (node (ref "J16") (pin "8") (pinfunction "8_8") (pintype "bidirectional"))
      (node (ref "J17") (pin "12") (pinfunction "12_12") (pintype "bidirectional"))
      (node (ref "J17") (pin "15") (pinfunction "15_15") (pintype "bidirectional"))
      (node (ref "J17") (pin "18") (pinfunction "18_18") (pintype "bidirectional"))
      (node (ref "J17") (pin "21") (pinfunction "21_21") (pintype "bidirectional"))
      (node (ref "J17") (pin "24") (pinfunction "24_24") (pintype "bidirectional"))
      (node (ref "J17") (pin "27") (pinfunction "27_27") (pintype "bidirectional"))
      (node (ref "J17") (pin "3") (pinfunction "3_3") (pintype "bidirectional"))
      (node (ref "J17") (pin "30") (pinfunction "30_30") (pintype "bidirectional"))
      (node (ref "J17") (pin "33") (pinfunction "33_33") (pintype "bidirectional"))
      (node (ref "J17") (pin "36") (pinfunction "36_36") (pintype "bidirectional"))
      (node (ref "J17") (pin "39") (pinfunction "39_39") (pintype "bidirectional"))
      (node (ref "J17") (pin "42") (pinfunction "42_42") (pintype "bidirectional"))
      (node (ref "J17") (pin "45") (pinfunction "45_45") (pintype "bidirectional"))
      (node (ref "J17") (pin "48") (pinfunction "48_48") (pintype "bidirectional"))
      (node (ref "J17") (pin "6") (pinfunction "6_6") (pintype "bidirectional"))
      (node (ref "J17") (pin "9") (pinfunction "9_9") (pintype "bidirectional"))
      (node (ref "J8") (pin "3") (pinfunction "3_3") (pintype "bidirectional"))
      (node (ref "J8") (pin "5") (pinfunction "5_5") (pintype "bidirectional"))
      (node (ref "J8") (pin "9") (pinfunction "9_9") (pintype "bidirectional"))
      (node (ref "R180") (pin "2") (pinfunction "2_2") (pintype "passive"))
      (node (ref "R181") (pin "2") (pinfunction "2_2") (pintype "passive"))
      (node (ref "R182") (pin "2") (pinfunction "2_2") (pintype "passive"))
      (node (ref "R183") (pin "2") (pinfunction "2_2") (pintype "passive"))
      (node (ref "R284") (pin "1") (pinfunction "1_1") (pintype "passive"))
      (node (ref "R285") (pin "1") (pinfunction "1_1") (pintype "passive"))
      (node (ref "R286") (pin "1") (pinfunction "1_1") (pintype "passive"))
      (node (ref "R291") (pin "1") (pinfunction "1_1") (pintype "passive"))
      (node (ref "R30") (pin "1") (pinfunction "1_1") (pintype "passive"))
      (node (ref "R96") (pin "2") (pinfunction "2_2") (pintype "passive"))
      (node (ref "T4") (pin "2") (pinfunction "S_2") (pintype "passive"))
    )
    (net (code "139") (name "Net-(D1-C)") (class "Default")
      (node (ref "D1") (pin "1") (pinfunction "C_1") (pintype "passive"))
      (node (ref "IC10") (pin "2") (pinfunction "~{RST}_2") (pintype "output"))
    )
    (net (code "140") (name "Net-(IC1-A0)") (class "Default")
      (node (ref "IC1") (pin "1") (pinfunction "A0_1") (pintype "input"))
      (node (ref "R286") (pin "2") (pinfunction "2_2") (pintype "passive"))
    )
    (net (code "141") (name "Net-(IC1-A1)") (class "Default")
      (node (ref "IC1") (pin "2") (pinfunction "A1_2") (pintype "input"))
      (node (ref "R285") (pin "2") (pinfunction "2_2") (pintype "passive"))
    )
    (net (code "142") (name "Net-(IC1-A2)") (class "Default")
      (node (ref "IC1") (pin "3") (pinfunction "A2_3") (pintype "input"))
      (node (ref "R284") (pin "2") (pinfunction "2_2") (pintype "passive"))
    )
    (net (code "143") (name "Net-(IC9A-PC9)") (class "Default")
      (node (ref "IC9") (pin "99") (pinfunction "PC9_99") (pintype "passive"))
      (node (ref "R176") (pin "2") (pinfunction "2_2") (pintype "passive"))
    )
    (net (code "144") (name "Net-(IC9B-PE7)") (class "Default")
      (node (ref "IC9") (pin "58") (pinfunction "PE7_58") (pintype "passive"))
      (node (ref "R186") (pin "1") (pinfunction "1_1") (pintype "passive"))
    )
    (net (code "145") (name "Net-(IC9B-PE8)") (class "Default")
      (node (ref "IC9") (pin "59") (pinfunction "PE8_59") (pintype "passive"))
      (node (ref "R187") (pin "1") (pinfunction "1_1") (pintype "passive"))
    )
    (net (code "146") (name "Net-(IC9B-PE9)") (class "Default")
      (node (ref "IC9") (pin "60") (pinfunction "PE9_60") (pintype "passive"))
      (node (ref "R188") (pin "1") (pinfunction "1_1") (pintype "passive"))
    )
    (net (code "147") (name "Net-(IC9B-PE10)") (class "Default")
      (node (ref "IC9") (pin "63") (pinfunction "PE10_63") (pintype "passive"))
      (node (ref "R189") (pin "1") (pinfunction "1_1") (pintype "passive"))
    )
    (net (code "148") (name "Net-(IC9B-PF10)") (class "Default")
      (node (ref "IC9") (pin "22") (pinfunction "PF10_22") (pintype "passive"))
      (node (ref "R128") (pin "2") (pinfunction "2_2") (pintype "passive"))
    )
    (net (code "149") (name "Net-(IC9C-BOOT0)") (class "Default")
      (node (ref "IC9") (pin "138") (pinfunction "BOOT0_138") (pintype "passive"))
      (node (ref "JP2") (pin "2") (pinfunction "E2_2") (pintype "passive"))
      (node (ref "R96") (pin "1") (pinfunction "1_1") (pintype "passive"))
    )
    (net (code "150") (name "Net-(IC9C-PDR_ON)") (class "Default")
      (node (ref "IC9") (pin "143") (pinfunction "PDR_ON_143") (pintype "passive"))
      (node (ref "R97") (pin "1") (pinfunction "1_1") (pintype "passive"))
    )
    (net (code "151") (name "Net-(IC9C-PH0{slash}OSC_IN)") (class "Default")
      (node (ref "C21") (pin "2") (pinfunction "2_2") (pintype "passive"))
      (node (ref "IC9") (pin "23") (pinfunction "PH0/OSC_IN_23") (pintype "passive"))
      (node (ref "Q1") (pin "2") (pinfunction "OSC2_2") (pintype "passive"))
    )
    (net (code "152") (name "Net-(IC9C-PH1{slash}OSC_OUT)") (class "Default")
      (node (ref "C23") (pin "2") (pinfunction "2_2") (pintype "passive"))
      (node (ref "IC9") (pin "24") (pinfunction "PH1/OSC_OUT_24") (pintype "passive"))
      (node (ref "Q1") (pin "1") (pinfunction "OSC1_1") (pintype "passive"))
    )
    (net (code "153") (name "Net-(IC9C-VCAP1)") (class "Default")
      (node (ref "C25") (pin "1") (pinfunction "1_1") (pintype "passive"))
      (node (ref "IC9") (pin "71") (pinfunction "VCAP1_71") (pintype "passive"))
    )
    (net (code "154") (name "Net-(IC9C-VCAP2)") (class "Default")
      (node (ref "C24") (pin "1") (pinfunction "1_1") (pintype "passive"))
      (node (ref "IC9") (pin "106") (pinfunction "VCAP2_106") (pintype "passive"))
    )
    (net (code "155") (name "Net-(IC9C-VREF+)") (class "Default")
      (node (ref "C14") (pin "2") (pinfunction "2_2") (pintype "passive"))
      (node (ref "C31") (pin "1") (pinfunction "1_1") (pintype "passive"))
      (node (ref "IC9") (pin "32") (pinfunction "VREF+_32") (pintype "passive"))
      (node (ref "R95") (pin "2") (pinfunction "2_2") (pintype "passive"))
    )
    (net (code "156") (name "P3V3") (class "Default")
      (node (ref "C1") (pin "2") (pinfunction "2_2") (pintype "passive"))
      (node (ref "C35") (pin "1") (pinfunction "1_1") (pintype "passive"))
      (node (ref "C37") (pin "1") (pinfunction "1_1") (pintype "passive"))
      (node (ref "C38") (pin "1") (pinfunction "1_1") (pintype "passive"))
      (node (ref "C41") (pin "1") (pinfunction "1_1") (pintype "passive"))
      (node (ref "C43") (pin "1") (pinfunction "1_1") (pintype "passive"))
      (node (ref "C57") (pin "1") (pinfunction "1_1") (pintype "passive"))
      (node (ref "C67") (pin "1") (pinfunction "1_1") (pintype "passive"))
      (node (ref "C70") (pin "1") (pinfunction "1_1") (pintype "passive"))
      (node (ref "C71") (pin "1") (pinfunction "1_1") (pintype "passive"))
      (node (ref "C72") (pin "1") (pinfunction "1_1") (pintype "passive"))
      (node (ref "C73") (pin "1") (pinfunction "1_1") (pintype "passive"))
      (node (ref "C74") (pin "1") (pinfunction "1_1") (pintype "passive"))
      (node (ref "C78") (pin "2") (pinfunction "2_2") (pintype "passive"))
      (node (ref "D28") (pin "5") (pinfunction "VBUS_5") (pintype "power_in"))
      (node (ref "IC1") (pin "8") (pinfunction "VCC_8") (pintype "power_in"))
      (node (ref "IC10") (pin "3") (pinfunction "Vcc_3") (pintype "power_in"))
      (node (ref "IC9") (pin "108") (pinfunction "VDD_2_108") (pintype "passive"))
      (node (ref "IC9") (pin "121") (pinfunction "VDD_10_121") (pintype "passive"))
      (node (ref "IC9") (pin "131") (pinfunction "VDD_11_131") (pintype "passive"))
      (node (ref "IC9") (pin "144") (pinfunction "VDD_3_144") (pintype "passive"))
      (node (ref "IC9") (pin "17") (pinfunction "VDD_5_17") (pintype "passive"))
      (node (ref "IC9") (pin "30") (pinfunction "VDD_12_30") (pintype "passive"))
      (node (ref "IC9") (pin "39") (pinfunction "VDD_4_39") (pintype "passive"))
      (node (ref "IC9") (pin "52") (pinfunction "VDD_6_52") (pintype "passive"))
      (node (ref "IC9") (pin "6") (pinfunction "VBAT_6") (pintype "passive"))
      (node (ref "IC9") (pin "62") (pinfunction "VDD_7_62") (pintype "passive"))
      (node (ref "IC9") (pin "72") (pinfunction "VDD_1_72") (pintype "passive"))
      (node (ref "IC9") (pin "84") (pinfunction "VDD_8_84") (pintype "passive"))
      (node (ref "IC9") (pin "95") (pinfunction "VDD33_USB_95") (pintype "passive"))
      (node (ref "J15") (pin "1") (pinfunction "1_1") (pintype "bidirectional"))
      (node (ref "J16") (pin "49") (pinfunction "49_49") (pintype "bidirectional"))
      (node (ref "J16") (pin "50") (pinfunction "50_50") (pintype "bidirectional"))
      (node (ref "J17") (pin "49") (pinfunction "49_49") (pintype "bidirectional"))
      (node (ref "J17") (pin "50") (pinfunction "50_50") (pintype "bidirectional"))
      (node (ref "J8") (pin "1") (pinfunction "1_1") (pintype "bidirectional"))
      (node (ref "JP2") (pin "1") (pinfunction "E1_1") (pintype "passive"))
      (node (ref "L15") (pin "1") (pinfunction "1_1") (pintype "passive"))
      (node (ref "R1") (pin "1") (pinfunction "1_1") (pintype "passive"))
      (node (ref "R12") (pin "2") (pinfunction "2_2") (pintype "passive"))
      (node (ref "R13") (pin "1") (pinfunction "1_1") (pintype "passive"))
      (node (ref "R131") (pin "1") (pinfunction "1_1") (pintype "passive"))
      (node (ref "R132") (pin "1") (pinfunction "1_1") (pintype "passive"))
      (node (ref "R136") (pin "1") (pinfunction "1_1") (pintype "passive"))
      (node (ref "R16") (pin "1") (pinfunction "1_1") (pintype "passive"))
      (node (ref "R2") (pin "1") (pinfunction "1_1") (pintype "passive"))
      (node (ref "R31") (pin "1") (pinfunction "1_1") (pintype "passive"))
      (node (ref "R33") (pin "1") (pinfunction "1_1") (pintype "passive"))
      (node (ref "R35") (pin "2") (pinfunction "2_2") (pintype "passive"))
      (node (ref "R95") (pin "1") (pinfunction "1_1") (pintype "passive"))
      (node (ref "R97") (pin "2") (pinfunction "2_2") (pintype "passive"))
      (node (ref "TP3") (pin "1") (pinfunction "1_1") (pintype "bidirectional"))
    )
    (net (code "157") (name "unconnected-(IC1-NC-Pad7)") (class "Default")
      (node (ref "IC1") (pin "7") (pinfunction "NC_7") (pintype "passive+no_connect"))
    )
    (net (code "158") (name "unconnected-(IC9B-PD2-Pad116)") (class "Default")
      (node (ref "IC9") (pin "116") (pinfunction "PD2_116") (pintype "passive+no_connect"))
    )
    (net (code "159") (name "unconnected-(IC9B-PD4-Pad118)") (class "Default")
      (node (ref "IC9") (pin "118") (pinfunction "PD4_118") (pintype "passive+no_connect"))
    )
    (net (code "160") (name "unconnected-(IC9B-PF11-Pad49)") (class "Default")
      (node (ref "IC9") (pin "49") (pinfunction "PF11_49") (pintype "passive+no_connect"))
    )
    (net (code "161") (name "unconnected-(J8-Pad7)") (class "Default")
      (node (ref "J8") (pin "7") (pinfunction "7_7") (pintype "bidirectional+no_connect"))
    )
  )
)
